# Power_Supply.net
KiCad netlist of a schematic drawn in Altium Designer
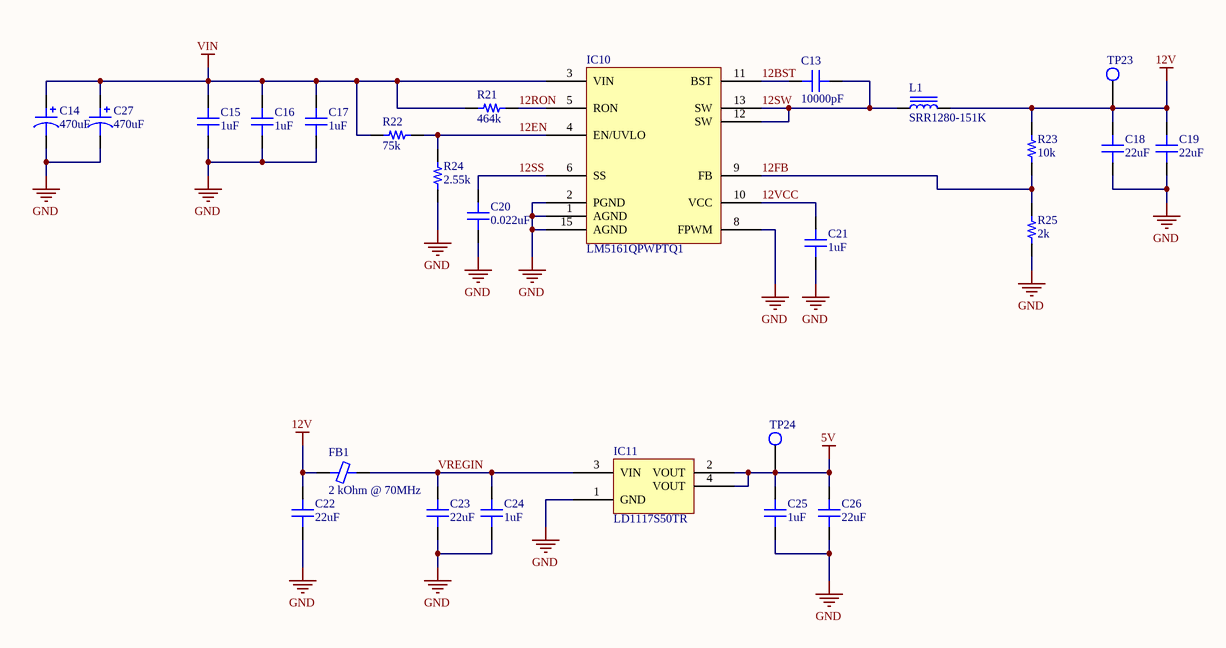
[diagram p0: Power Supply.SchDoc]

(export (version "E")
  (design (tool "Eeschema 10.0.6"))
  (components
    (comp (ref "C13")
      (value "10000pF")
      (footprint "CAP 0603/1608")
      (description "CAP CER 10000PF 50V X7R 0603")
      (fields
        (field (name "PART NUMBER") "CL10B103KB8NCNC")
        (field (name "MANUFACTURER") "Samsung Electro-Mechanics America, Inc.")
      )
      (libsource (lib "Celestial Library Database") (part "Capacitor"))
    )
    (comp (ref "C14")
      (value "470uF")
      (footprint "CAP AL TH D25 L12.5 H32")
      (description "CAP ALUM 470UF 20% 160V RADIAL")
      (fields (field (name "PART NUMBER") "UVR2C471MRD6") (field (name "MANUFACTURER") "Nichicon"))
      (libsource (lib "Celestial Library Database") (part "Polarised Capacitor"))
    )
    (comp (ref "C15")
      (value "1uF")
      (footprint "CAP 1812/4532 2.8MM")
      (description "CAP CER 1UF 250V X7T 1812")
      (fields
        (field (name "PART NUMBER") "C4532X7T2E105M250KA")
        (field (name "MANUFACTURER") "TDK Corporation")
      )
      (libsource (lib "Celestial Library Database") (part "Capacitor"))
    )
    (comp (ref "C16")
      (value "1uF")
      (footprint "CAP 1812/4532 2.8MM")
      (description "CAP CER 1UF 250V X7T 1812")
      (fields
        (field (name "PART NUMBER") "C4532X7T2E105M250KA")
        (field (name "MANUFACTURER") "TDK Corporation")
      )
      (libsource (lib "Celestial Library Database") (part "Capacitor"))
    )
    (comp (ref "C17")
      (value "1uF")
      (footprint "CAP 1812/4532 2.8MM")
      (description "CAP CER 1UF 250V X7T 1812")
      (fields
        (field (name "PART NUMBER") "C4532X7T2E105M250KA")
        (field (name "MANUFACTURER") "TDK Corporation")
      )
      (libsource (lib "Celestial Library Database") (part "Capacitor"))
    )
    (comp (ref "C18")
      (value "22uF")
      (footprint "CAP 1206/3216")
      (description "CAP CER 22UF 16V X5R 1206")
      (fields
        (field (name "PART NUMBER") "CL31A226MOCLNNC")
        (field (name "MANUFACTURER") "Samsung Electro-Mechanics America, Inc.")
      )
      (libsource (lib "Celestial Library Database") (part "Capacitor"))
    )
    (comp (ref "C19")
      (value "22uF")
      (footprint "CAP 1206/3216")
      (description "CAP CER 22UF 16V X5R 1206")
      (fields
        (field (name "PART NUMBER") "CL31A226MOCLNNC")
        (field (name "MANUFACTURER") "Samsung Electro-Mechanics America, Inc.")
      )
      (libsource (lib "Celestial Library Database") (part "Capacitor"))
    )
    (comp (ref "C20")
      (value "0.022uF")
      (footprint "CAP 0603/1608")
      (description "CAP CER 0.022UF 50V X7R 0603")
      (fields
        (field (name "PART NUMBER") "CL10B223KB8NNNC")
        (field (name "MANUFACTURER") "Samsung Electro-Mechanics America, Inc.")
      )
      (libsource (lib "Celestial Library Database") (part "Capacitor"))
    )
    (comp (ref "C21")
      (value "1uF")
      (footprint "CAP 0603/1608")
      (description "CAP CER 1UF 16V X5R 0603")
      (fields
        (field (name "PART NUMBER") "CL10A105KO8NNNC")
        (field (name "MANUFACTURER") "Samsung Electro-Mechanics America, Inc.")
      )
      (libsource (lib "Celestial Library Database") (part "Capacitor"))
    )
    (comp (ref "C22")
      (value "22uF")
      (footprint "CAP 1206/3216")
      (description "CAP CER 22UF 16V X5R 1206")
      (fields
        (field (name "PART NUMBER") "CL31A226MOCLNNC")
        (field (name "MANUFACTURER") "Samsung Electro-Mechanics America, Inc.")
      )
      (libsource (lib "Celestial Library Database") (part "Capacitor"))
    )
    (comp (ref "C23")
      (value "22uF")
      (footprint "CAP 1206/3216")
      (description "CAP CER 22UF 16V X5R 1206")
      (fields
        (field (name "PART NUMBER") "CL31A226MOCLNNC")
        (field (name "MANUFACTURER") "Samsung Electro-Mechanics America, Inc.")
      )
      (libsource (lib "Celestial Library Database") (part "Capacitor"))
    )
    (comp (ref "C24")
      (value "1uF")
      (footprint "CAP 0603/1608")
      (description "CAP CER 1UF 16V X5R 0603")
      (fields
        (field (name "PART NUMBER") "CL10A105KO8NNNC")
        (field (name "MANUFACTURER") "Samsung Electro-Mechanics America, Inc.")
      )
      (libsource (lib "Celestial Library Database") (part "Capacitor"))
    )
    (comp (ref "C25")
      (value "1uF")
      (footprint "CAP 0603/1608")
      (description "CAP CER 1UF 16V X5R 0603")
      (fields
        (field (name "PART NUMBER") "CL10A105KO8NNNC")
        (field (name "MANUFACTURER") "Samsung Electro-Mechanics America, Inc.")
      )
      (libsource (lib "Celestial Library Database") (part "Capacitor"))
    )
    (comp (ref "C26")
      (value "22uF")
      (footprint "CAP 1206/3216")
      (description "CAP CER 22UF 16V X5R 1206")
      (fields
        (field (name "PART NUMBER") "CL31A226MOCLNNC")
        (field (name "MANUFACTURER") "Samsung Electro-Mechanics America, Inc.")
      )
      (libsource (lib "Celestial Library Database") (part "Capacitor"))
    )
    (comp (ref "C27")
      (value "470uF")
      (footprint "CAP AL TH D25 L12.5 H32")
      (description "CAP ALUM 470UF 20% 160V RADIAL")
      (fields (field (name "PART NUMBER") "UVR2C471MRD6") (field (name "MANUFACTURER") "Nichicon"))
      (libsource (lib "Celestial Library Database") (part "Polarised Capacitor"))
    )
    (comp (ref "FB1")
      (value "2 kOhm @ 70MHz")
      (footprint "FER 0805/2012")
      (description "FERRITE CHIP 2000 OHM 500MA 0805")
      (fields
        (field (name "PART NUMBER") "CIM21J202NE")
        (field (name "MANUFACTURER") "Samsung Electro-Mechanics America, Inc.")
      )
      (libsource (lib "Celestial Library Database") (part "Ferrite Chip"))
    )
    (comp (ref "IC10")
      (value "LM5161QPWPTQ1")
      (footprint "TI HTSSOP-14 PWP")
      (description "IC REG BCK FLYBCK ISO 14HTSSOP")
      (fields (field (name "MANUFACTURER") "Texas Instruments"))
      (libsource (lib "Celestial Library Database") (part "TI LM5161"))
    )
    (comp (ref "IC11")
      (value "LD1117S50TR")
      (footprint "ST SOT-223")
      (description "IC REG LDO 5V 0.8A SOT223")
      (fields (field (name "MANUFACTURER") "STMicroelectronics"))
      (libsource (lib "Celestial Library Database") (part "ST LD1117"))
    )
    (comp (ref "L1")
      (value "SRR1280-151K")
      (footprint "BOURNS SRR1280")
      (description "FIXED IND 150UH 1.85A 270 MOHM")
      (fields (field (name "MANUFACTURER") "Bourns Inc.") (field (name "TOLERANCE") "10%"))
      (libsource (lib "Celestial Library Database") (part "Inductor"))
    )
    (comp (ref "R21")
      (value "464k")
      (footprint "RES 0603/1608")
      (description "RES SMD 464K OHM 1% 1/10W 0603")
      (fields
        (field (name "PART NUMBER") "ERJ-3EKF4643V")
        (field (name "MANUFACTURER") "Panasonic Electronic Components")
      )
      (libsource (lib "Celestial Library Database") (part "Resistor"))
    )
    (comp (ref "R22")
      (value "75k")
      (footprint "RES 0603/1608")
      (description "RES SMD 75K OHM 1% 1/10W 0603")
      (fields
        (field (name "PART NUMBER") "ERJ-3EKF7502V")
        (field (name "MANUFACTURER") "Panasonic Electronic Components")
      )
      (libsource (lib "Celestial Library Database") (part "Resistor"))
    )
    (comp (ref "R23")
      (value "10k")
      (footprint "RES 0603/1608")
      (description "RES SMD 10K OHM 1% 1/10W 0603")
      (fields
        (field (name "PART NUMBER") "ERJ-3EKF1002V")
        (field (name "MANUFACTURER") "Panasonic Electronic Components")
      )
      (libsource (lib "Celestial Library Database") (part "Resistor"))
    )
    (comp (ref "R24")
      (value "2.55k")
      (footprint "RES 0603/1608")
      (description "RES SMD 2.55K OHM 1% 1/10W 0603")
      (fields
        (field (name "PART NUMBER") "ERJ-3EKF2551V")
        (field (name "MANUFACTURER") "Panasonic Electronic Components")
      )
      (libsource (lib "Celestial Library Database") (part "Resistor"))
    )
    (comp (ref "R25")
      (value "2k")
      (footprint "RES 0603/1608")
      (description "RES SMD 2K OHM 1% 1/10W 0603")
      (fields
        (field (name "PART NUMBER") "ERJ-3EKF2001V")
        (field (name "MANUFACTURER") "Panasonic Electronic Components")
      )
      (libsource (lib "Celestial Library Database") (part "Resistor"))
    )
    (comp (ref "TP23")
      (value "Test Point")
      (footprint "Test Point")
      (libsource (lib "Motor Controller") (part "Test Point"))
    )
    (comp (ref "TP24")
      (value "Test Point")
      (footprint "Test Point")
      (libsource (lib "Motor Controller") (part "Test Point"))
    )
  )
  (nets
    (net (code "1") (name "/12BST") (class "Default")
      (node (ref "C13") (pin "1") (pinfunction "1_1") (pintype "passive"))
      (node (ref "IC10") (pin "11") (pinfunction "BST_11") (pintype "passive"))
    )
    (net (code "2") (name "/12EN") (class "Default")
      (node (ref "IC10") (pin "4") (pinfunction "EN/UVLO_4") (pintype "passive"))
      (node (ref "R22") (pin "1") (pinfunction "1_1") (pintype "passive"))
      (node (ref "R24") (pin "2") (pinfunction "2_2") (pintype "passive"))
    )
    (net (code "3") (name "/12FB") (class "Default")
      (node (ref "IC10") (pin "9") (pinfunction "FB_9") (pintype "passive"))
      (node (ref "R23") (pin "1") (pinfunction "1_1") (pintype "passive"))
      (node (ref "R25") (pin "2") (pinfunction "2_2") (pintype "passive"))
    )
    (net (code "4") (name "/12RON") (class "Default")
      (node (ref "IC10") (pin "5") (pinfunction "RON_5") (pintype "passive"))
      (node (ref "R21") (pin "2") (pinfunction "2_2") (pintype "passive"))
    )
    (net (code "5") (name "/12SS") (class "Default")
      (node (ref "C20") (pin "2") (pinfunction "2_2") (pintype "passive"))
      (node (ref "IC10") (pin "6") (pinfunction "SS_6") (pintype "passive"))
    )
    (net (code "6") (name "/12SW") (class "Default")
      (node (ref "C13") (pin "2") (pinfunction "2_2") (pintype "passive"))
      (node (ref "IC10") (pin "12") (pinfunction "SW_12") (pintype "passive"))
      (node (ref "IC10") (pin "13") (pinfunction "SW_13") (pintype "passive"))
      (node (ref "L1") (pin "1") (pinfunction "1_1") (pintype "passive"))
    )
    (net (code "7") (name "/12VCC") (class "Default")
      (node (ref "C21") (pin "2") (pinfunction "2_2") (pintype "passive"))
      (node (ref "IC10") (pin "10") (pinfunction "VCC_10") (pintype "passive"))
    )
    (net (code "8") (name "/VREGIN") (class "Default")
      (node (ref "C23") (pin "2") (pinfunction "2_2") (pintype "passive"))
      (node (ref "C24") (pin "2") (pinfunction "2_2") (pintype "passive"))
      (node (ref "FB1") (pin "2") (pinfunction "2_2") (pintype "passive"))
      (node (ref "IC11") (pin "3") (pinfunction "VIN_3") (pintype "passive"))
    )
    (net (code "9") (name "5V") (class "Default")
      (node (ref "C25") (pin "2") (pinfunction "2_2") (pintype "passive"))
      (node (ref "C26") (pin "2") (pinfunction "2_2") (pintype "passive"))
      (node (ref "IC11") (pin "2") (pinfunction "VOUT_2") (pintype "passive"))
      (node (ref "IC11") (pin "4") (pinfunction "VOUT_4") (pintype "passive"))
      (node (ref "TP24") (pin "1") (pinfunction "TP_1") (pintype "passive"))
    )
    (net (code "10") (name "12V") (class "Default")
      (node (ref "C18") (pin "2") (pinfunction "2_2") (pintype "passive"))
      (node (ref "C19") (pin "2") (pinfunction "2_2") (pintype "passive"))
      (node (ref "C22") (pin "2") (pinfunction "2_2") (pintype "passive"))
      (node (ref "FB1") (pin "1") (pinfunction "1_1") (pintype "passive"))
      (node (ref "L1") (pin "2") (pinfunction "2_2") (pintype "passive"))
      (node (ref "R23") (pin "2") (pinfunction "2_2") (pintype "passive"))
      (node (ref "TP23") (pin "1") (pinfunction "TP_1") (pintype "passive"))
    )
    (net (code "11") (name "GND") (class "Default")
      (node (ref "C14") (pin "2") (pinfunction "2_2") (pintype "passive"))
      (node (ref "C15") (pin "1") (pinfunction "1_1") (pintype "passive"))
      (node (ref "C16") (pin "1") (pinfunction "1_1") (pintype "passive"))
      (node (ref "C17") (pin "1") (pinfunction "1_1") (pintype "passive"))
      (node (ref "C18") (pin "1") (pinfunction "1_1") (pintype "passive"))
      (node (ref "C19") (pin "1") (pinfunction "1_1") (pintype "passive"))
      (node (ref "C20") (pin "1") (pinfunction "1_1") (pintype "passive"))
      (node (ref "C21") (pin "1") (pinfunction "1_1") (pintype "passive"))
      (node (ref "C22") (pin "1") (pinfunction "1_1") (pintype "passive"))
      (node (ref "C23") (pin "1") (pinfunction "1_1") (pintype "passive"))
      (node (ref "C24") (pin "1") (pinfunction "1_1") (pintype "passive"))
      (node (ref "C25") (pin "1") (pinfunction "1_1") (pintype "passive"))
      (node (ref "C26") (pin "1") (pinfunction "1_1") (pintype "passive"))
      (node (ref "C27") (pin "2") (pinfunction "2_2") (pintype "passive"))
      (node (ref "IC10") (pin "1") (pinfunction "AGND_1") (pintype "passive"))
      (node (ref "IC10") (pin "15") (pinfunction "AGND_15") (pintype "passive"))
      (node (ref "IC10") (pin "2") (pinfunction "PGND_2") (pintype "passive"))
      (node (ref "IC10") (pin "8") (pinfunction "FPWM_8") (pintype "passive"))
      (node (ref "IC11") (pin "1") (pinfunction "GND_1") (pintype "passive"))
      (node (ref "R24") (pin "1") (pinfunction "1_1") (pintype "passive"))
      (node (ref "R25") (pin "1") (pinfunction "1_1") (pintype "passive"))
    )
    (net (code "12") (name "VIN") (class "Default")
      (node (ref "C14") (pin "1") (pinfunction "1_1") (pintype "passive"))
      (node (ref "C15") (pin "2") (pinfunction "2_2") (pintype "passive"))
      (node (ref "C16") (pin "2") (pinfunction "2_2") (pintype "passive"))
      (node (ref "C17") (pin "2") (pinfunction "2_2") (pintype "passive"))
      (node (ref "C27") (pin "1") (pinfunction "1_1") (pintype "passive"))
      (node (ref "IC10") (pin "3") (pinfunction "VIN_3") (pintype "passive"))
      (node (ref "R21") (pin "1") (pinfunction "1_1") (pintype "passive"))
      (node (ref "R22") (pin "2") (pinfunction "2_2") (pintype "passive"))
    )
  )
)
